# ArmLeap.net
KiCad netlist of a schematic drawn in EAGLE
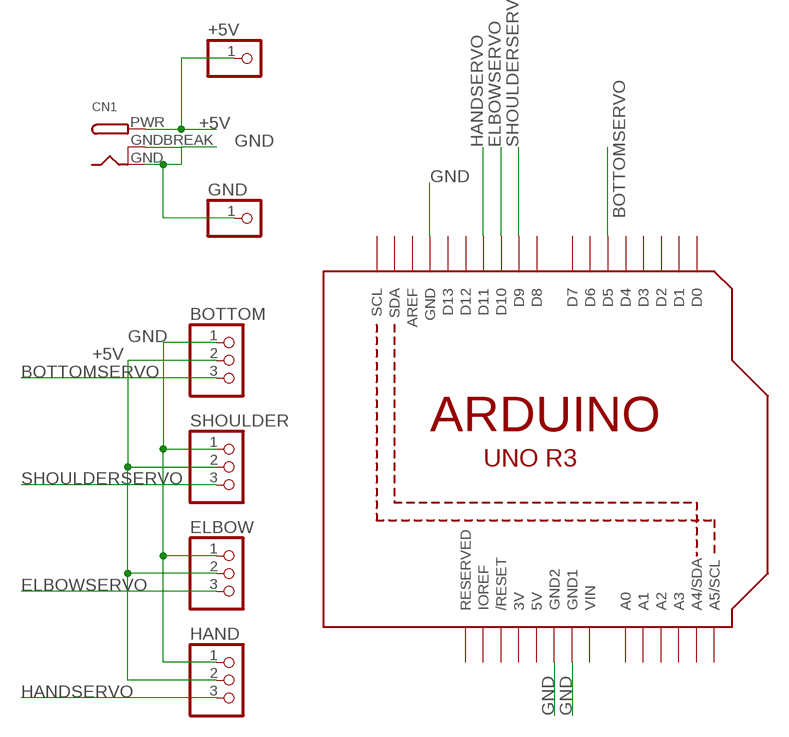
[diagram p0: schematic, sheet 1]

(export (version "E")
  (design (tool "Eeschema 10.0.6"))
  (components
    (comp (ref "+5V")
      (value "PINHD-1X1")
      (footprint "eagle-import:1X01")
      (libsource (lib "eagle-import") (part "PINHD-1X1"))
    )
    (comp (ref "BOTTOM")
      (value "PINHD-1X3")
      (footprint "eagle-import:1X03")
      (libsource (lib "eagle-import") (part "PINHD-1X3"))
    )
    (comp (ref "CN1")
      (value "DCBARRELPTH")
      (footprint "eagle-import:DCJACK_2MM_PTH")
      (libsource (lib "eagle-import") (part "DCBARRELPTH"))
    )
    (comp (ref "ELBOW")
      (value "PINHD-1X3")
      (footprint "eagle-import:1X03")
      (libsource (lib "eagle-import") (part "PINHD-1X3"))
    )
    (comp (ref "GND")
      (value "PINHD-1X1")
      (footprint "eagle-import:1X01")
      (libsource (lib "eagle-import") (part "PINHD-1X1"))
    )
    (comp (ref "HAND")
      (value "PINHD-1X3")
      (footprint "eagle-import:1X03")
      (libsource (lib "eagle-import") (part "PINHD-1X3"))
    )
    (comp (ref "SHOULDER")
      (value "PINHD-1X3")
      (footprint "eagle-import:1X03")
      (libsource (lib "eagle-import") (part "PINHD-1X3"))
    )
    (comp (ref "U1")
      (value "ARDUINOR3-DIMENSION")
      (footprint "eagle-import:ARDUINOR3")
      (libsource (lib "eagle-import") (part "ARDUINOR3-DIMENSION"))
    )
  )
  (nets
    (net (code "1") (name "/+5V") (class "Default")
      (node (ref "+5V") (pin "1") (pinfunction "1_1") (pintype "passive"))
      (node (ref "BOTTOM") (pin "2") (pinfunction "2_2") (pintype "passive"))
      (node (ref "CN1") (pin "PWR") (pinfunction "PWR_PWR") (pintype "power_in"))
      (node (ref "ELBOW") (pin "2") (pinfunction "2_2") (pintype "passive"))
      (node (ref "HAND") (pin "2") (pinfunction "2_2") (pintype "passive"))
      (node (ref "SHOULDER") (pin "2") (pinfunction "2_2") (pintype "passive"))
    )
    (net (code "2") (name "/3V") (class "Default")
      (node (ref "U1") (pin "3V") (pinfunction "3V_3V") (pintype "power_in"))
    )
    (net (code "3") (name "/5V") (class "Default")
      (node (ref "U1") (pin "5V") (pinfunction "5V_5V") (pintype "power_in"))
    )
    (net (code "4") (name "/BOTTOMSERVO") (class "Default")
      (node (ref "BOTTOM") (pin "3") (pinfunction "3_3") (pintype "passive"))
      (node (ref "U1") (pin "D5") (pinfunction "D5_D5") (pintype "bidirectional"))
    )
    (net (code "5") (name "/ELBOWSERVO") (class "Default")
      (node (ref "ELBOW") (pin "3") (pinfunction "3_3") (pintype "passive"))
      (node (ref "U1") (pin "D10") (pinfunction "D10_D10") (pintype "bidirectional"))
    )
    (net (code "6") (name "/GND") (class "Default")
      (node (ref "BOTTOM") (pin "1") (pinfunction "1_1") (pintype "passive"))
      (node (ref "CN1") (pin "GND") (pinfunction "GND_GND") (pintype "power_in"))
      (node (ref "CN1") (pin "GNDBREAK") (pinfunction "GNDBREAK_GNDBREAK") (pintype "power_in"))
      (node (ref "ELBOW") (pin "1") (pinfunction "1_1") (pintype "passive"))
      (node (ref "GND") (pin "1") (pinfunction "1_1") (pintype "passive"))
      (node (ref "HAND") (pin "1") (pinfunction "1_1") (pintype "passive"))
      (node (ref "SHOULDER") (pin "1") (pinfunction "1_1") (pintype "passive"))
      (node (ref "U1") (pin "GND") (pinfunction "GND_GND") (pintype "power_in"))
      (node (ref "U1") (pin "GND1") (pinfunction "GND1_GND1") (pintype "power_in"))
      (node (ref "U1") (pin "GND2") (pinfunction "GND2_GND2") (pintype "power_in"))
    )
    (net (code "7") (name "/HANDSERVO") (class "Default")
      (node (ref "HAND") (pin "3") (pinfunction "3_3") (pintype "passive"))
      (node (ref "U1") (pin "D11") (pinfunction "D11_D11") (pintype "bidirectional"))
    )
    (net (code "8") (name "/SHOULDERSERVO") (class "Default")
      (node (ref "SHOULDER") (pin "3") (pinfunction "3_3") (pintype "passive"))
      (node (ref "U1") (pin "D9") (pinfunction "D9_D9") (pintype "bidirectional"))
    )
    (net (code "9") (name "/VIN") (class "Default")
      (node (ref "U1") (pin "VIN") (pinfunction "VIN_VIN") (pintype "power_in"))
    )
    (net (code "10") (name "unconnected-(U1-A4{slash}SDA-PadA4)") (class "Default")
      (node (ref "U1") (pin "A4") (pinfunction "A4/SDA_A4") (pintype "bidirectional"))
    )
    (net (code "11") (name "unconnected-(U1-A5{slash}SCL-PadA5)") (class "Default")
      (node (ref "U1") (pin "A5") (pinfunction "A5/SCL_A5") (pintype "bidirectional"))
    )
    (net (code "12") (name "unconnected-(U1-PadA0)") (class "Default")
      (node (ref "U1") (pin "A0") (pinfunction "A0_A0") (pintype "bidirectional"))
    )
    (net (code "13") (name "unconnected-(U1-PadA1)") (class "Default")
      (node (ref "U1") (pin "A1") (pinfunction "A1_A1") (pintype "bidirectional"))
    )
    (net (code "14") (name "unconnected-(U1-PadA2)") (class "Default")
      (node (ref "U1") (pin "A2") (pinfunction "A2_A2") (pintype "bidirectional"))
    )
    (net (code "15") (name "unconnected-(U1-PadA3)") (class "Default")
      (node (ref "U1") (pin "A3") (pinfunction "A3_A3") (pintype "bidirectional"))
    )
    (net (code "16") (name "unconnected-(U1-PadAREF)") (class "Default")
      (node (ref "U1") (pin "AREF") (pinfunction "AREF_AREF") (pintype "bidirectional"))
    )
    (net (code "17") (name "unconnected-(U1-PadD0)") (class "Default")
      (node (ref "U1") (pin "D0") (pinfunction "D0_D0") (pintype "bidirectional"))
    )
    (net (code "18") (name "unconnected-(U1-PadD1)") (class "Default")
      (node (ref "U1") (pin "D1") (pinfunction "D1_D1") (pintype "bidirectional"))
    )
    (net (code "19") (name "unconnected-(U1-PadD2)") (class "Default")
      (node (ref "U1") (pin "D2") (pinfunction "D2_D2") (pintype "bidirectional"))
    )
    (net (code "20") (name "unconnected-(U1-PadD3)") (class "Default")
      (node (ref "U1") (pin "D3") (pinfunction "D3_D3") (pintype "bidirectional"))
    )
    (net (code "21") (name "unconnected-(U1-PadD4)") (class "Default")
      (node (ref "U1") (pin "D4") (pinfunction "D4_D4") (pintype "bidirectional"))
    )
    (net (code "22") (name "unconnected-(U1-PadD6)") (class "Default")
      (node (ref "U1") (pin "D6") (pinfunction "D6_D6") (pintype "bidirectional"))
    )
    (net (code "23") (name "unconnected-(U1-PadD7)") (class "Default")
      (node (ref "U1") (pin "D7") (pinfunction "D7_D7") (pintype "bidirectional"))
    )
    (net (code "24") (name "unconnected-(U1-PadD8)") (class "Default")
      (node (ref "U1") (pin "D8") (pinfunction "D8_D8") (pintype "bidirectional"))
    )
    (net (code "25") (name "unconnected-(U1-PadD12)") (class "Default")
      (node (ref "U1") (pin "D12") (pinfunction "D12_D12") (pintype "bidirectional"))
    )
    (net (code "26") (name "unconnected-(U1-PadD13)") (class "Default")
      (node (ref "U1") (pin "D13") (pinfunction "D13_D13") (pintype "bidirectional"))
    )
    (net (code "27") (name "unconnected-(U1-PadIOREF)") (class "Default")
      (node (ref "U1") (pin "IOREF") (pinfunction "IOREF_IOREF") (pintype "output"))
    )
    (net (code "28") (name "unconnected-(U1-PadRESERVED)") (class "Default")
      (node (ref "U1") (pin "RESERVED") (pinfunction "RESERVED_RESERVED") (pintype "no_connect"))
    )
    (net (code "29") (name "unconnected-(U1-PadSCL)") (class "Default")
      (node (ref "U1") (pin "SCL") (pinfunction "SCL_SCL") (pintype "bidirectional"))
    )
    (net (code "30") (name "unconnected-(U1-PadSDA)") (class "Default")
      (node (ref "U1") (pin "SDA") (pinfunction "SDA_SDA") (pintype "bidirectional"))
    )
    (net (code "31") (name "unconnected-(U1-{slash}RESET-PadRESET)") (class "Default")
      (node (ref "U1") (pin "RESET") (pinfunction "/RESET_RESET") (pintype "bidirectional"))
    )
  )
)
